# 11-Ice40_FPGA.net
KiCad netlist of a schematic drawn in Altium Designer
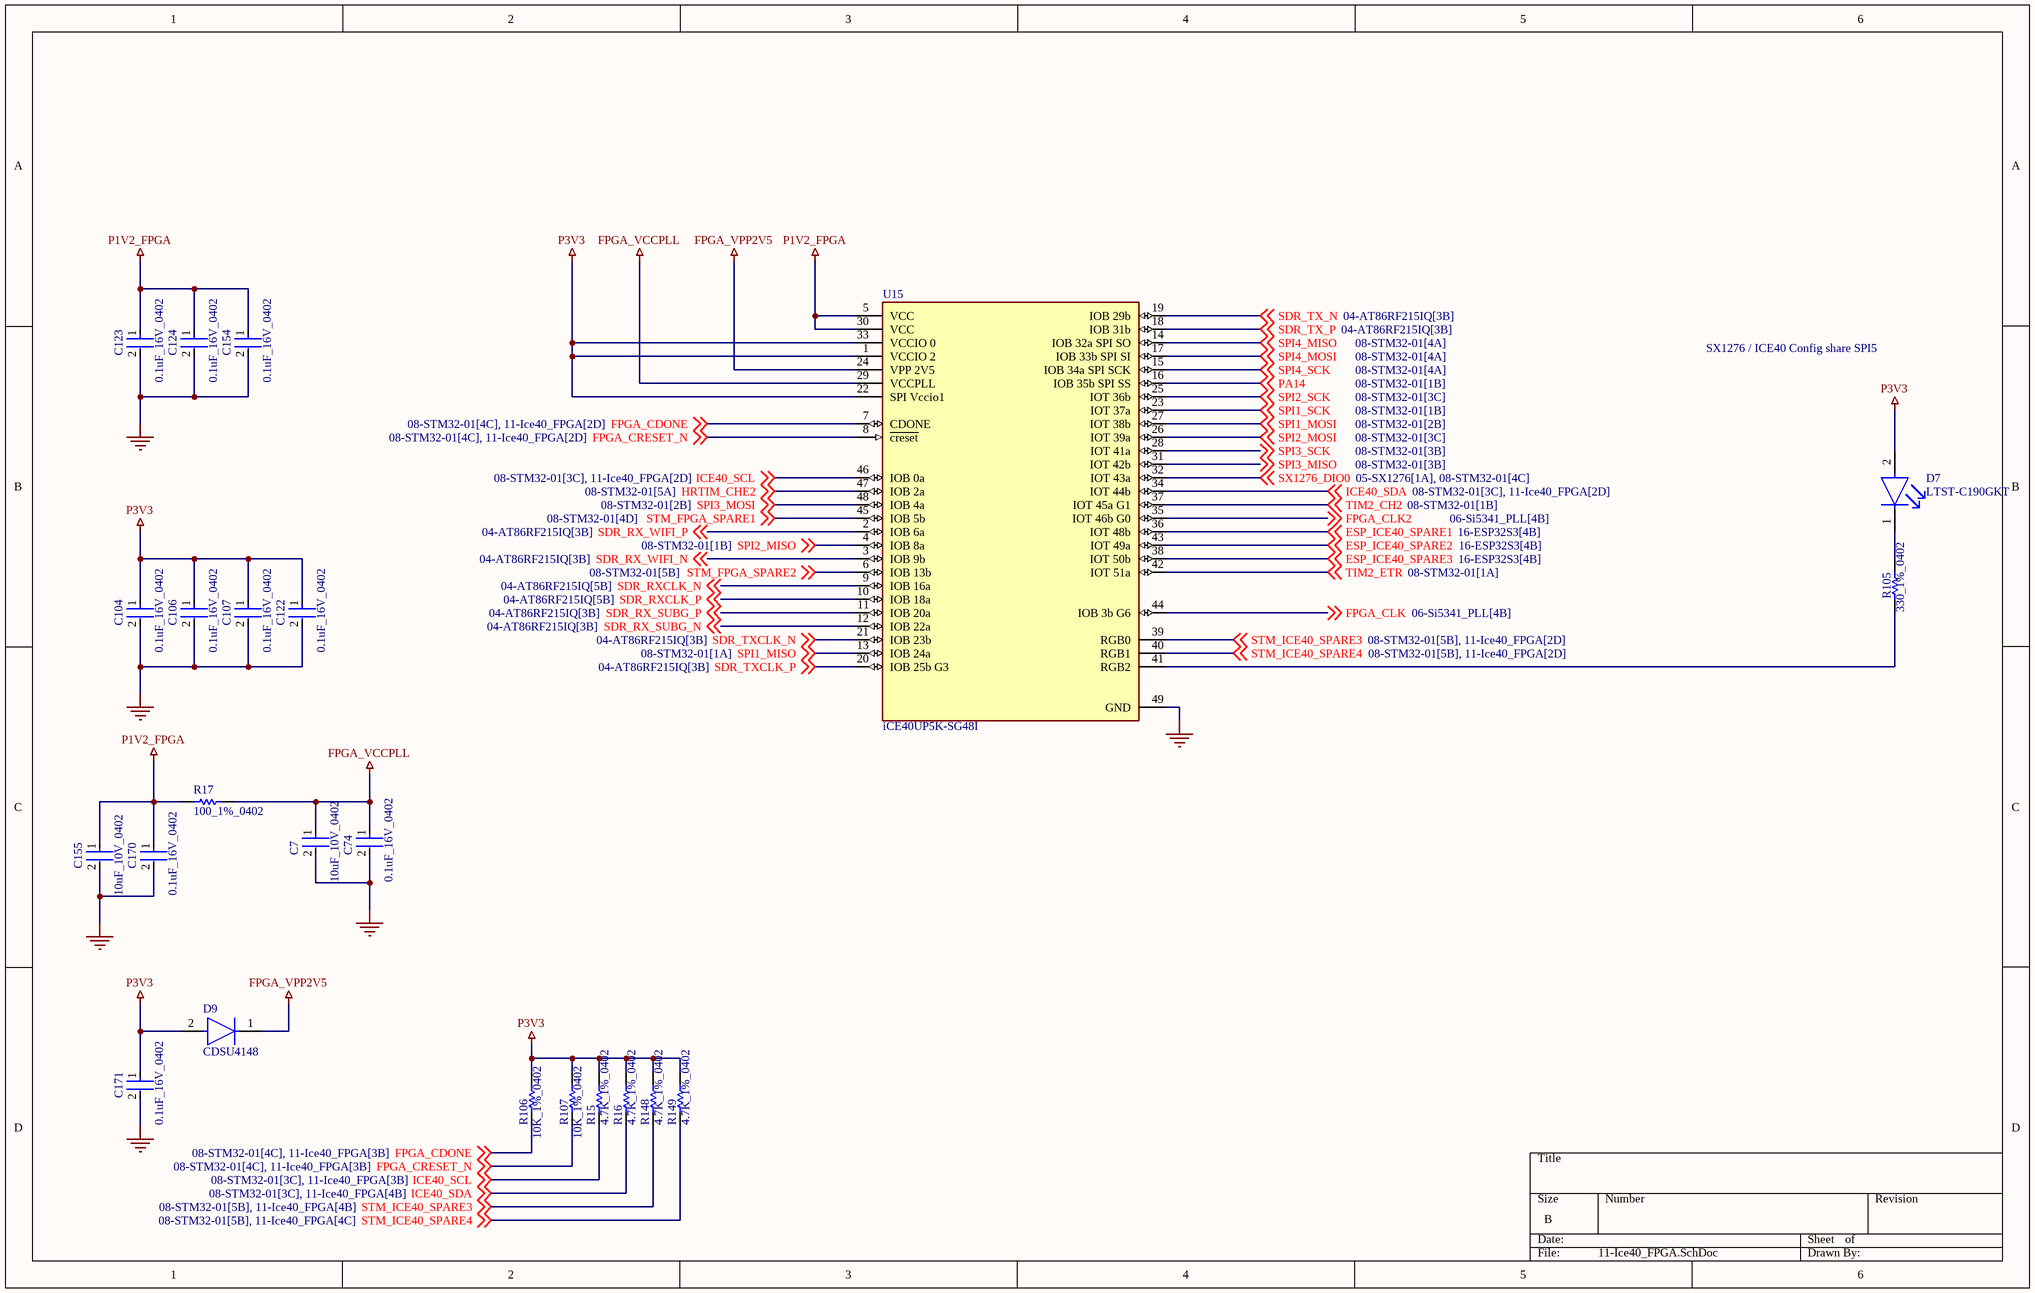
[diagram p0: 11-Ice40_FPGA.SchDoc]

(export (version "E")
  (design (tool "Eeschema 10.0.6"))
  (components
    (comp (ref "C7")
      (value "10uF_10V_0402")
      (footprint "FP-CL05A106MP5NUNC-MFG")
      (description "CAP CER 10UF 10V X5R 0402")
      (fields
        (field (name "OCTOPART") "https://octopart.com/cl05a106mp5nunc-samsung-22457395")
        (field (name "TOLERANCE") "20%")
      )
      (libsource (lib "Altium Content Vault") (part "b4654b650e69147ec39a6b967a45e02"))
    )
    (comp (ref "C74")
      (value "0.1uF_16V_0402")
      (footprint "FP-C0402-BB-MFG")
      (description "CAP CER 0.1UF 16V 5% X7R 0402")
      (fields
        (field (name "MANUFACTURER") "Kemet")
        (field (name "MANUFACTURER PART NUMBER") "C0402C104J4RACTU")
      )
      (libsource (lib "Altium Content Vault") (part "b4654b650e69147ec39a6b967a45e02"))
    )
    (comp (ref "C104")
      (value "0.1uF_16V_0402")
      (footprint "FP-C0402-BB-MFG")
      (description "CAP CER 0.1UF 16V 5% X7R 0402")
      (fields
        (field (name "MANUFACTURER") "Kemet")
        (field (name "MANUFACTURER PART NUMBER") "C0402C104J4RACTU")
      )
      (libsource (lib "Altium Content Vault") (part "b4654b650e69147ec39a6b967a45e02"))
    )
    (comp (ref "C106")
      (value "0.1uF_16V_0402")
      (footprint "FP-C0402-BB-MFG")
      (description "CAP CER 0.1UF 16V 5% X7R 0402")
      (fields
        (field (name "MANUFACTURER") "Kemet")
        (field (name "MANUFACTURER PART NUMBER") "C0402C104J4RACTU")
      )
      (libsource (lib "Altium Content Vault") (part "b4654b650e69147ec39a6b967a45e02"))
    )
    (comp (ref "C107")
      (value "0.1uF_16V_0402")
      (footprint "FP-C0402-BB-MFG")
      (description "CAP CER 0.1UF 16V 5% X7R 0402")
      (fields
        (field (name "MANUFACTURER") "Kemet")
        (field (name "MANUFACTURER PART NUMBER") "C0402C104J4RACTU")
      )
      (libsource (lib "Altium Content Vault") (part "b4654b650e69147ec39a6b967a45e02"))
    )
    (comp (ref "C122")
      (value "0.1uF_16V_0402")
      (footprint "FP-C0402-BB-MFG")
      (description "CAP CER 0.1UF 16V 5% X7R 0402")
      (fields
        (field (name "MANUFACTURER") "Kemet")
        (field (name "MANUFACTURER PART NUMBER") "C0402C104J4RACTU")
      )
      (libsource (lib "Altium Content Vault") (part "b4654b650e69147ec39a6b967a45e02"))
    )
    (comp (ref "C123")
      (value "0.1uF_16V_0402")
      (footprint "FP-C0402-BB-MFG")
      (description "CAP CER 0.1UF 16V 5% X7R 0402")
      (fields
        (field (name "MANUFACTURER") "Kemet")
        (field (name "MANUFACTURER PART NUMBER") "C0402C104J4RACTU")
      )
      (libsource (lib "Altium Content Vault") (part "b4654b650e69147ec39a6b967a45e02"))
    )
    (comp (ref "C124")
      (value "0.1uF_16V_0402")
      (footprint "FP-C0402-BB-MFG")
      (description "CAP CER 0.1UF 16V 5% X7R 0402")
      (fields
        (field (name "MANUFACTURER") "Kemet")
        (field (name "MANUFACTURER PART NUMBER") "C0402C104J4RACTU")
      )
      (libsource (lib "Altium Content Vault") (part "b4654b650e69147ec39a6b967a45e02"))
    )
    (comp (ref "C154")
      (value "0.1uF_16V_0402")
      (footprint "FP-C0402-BB-MFG")
      (description "CAP CER 0.1UF 16V 5% X7R 0402")
      (fields
        (field (name "MANUFACTURER") "Kemet")
        (field (name "MANUFACTURER PART NUMBER") "C0402C104J4RACTU")
      )
      (libsource (lib "Altium Content Vault") (part "b4654b650e69147ec39a6b967a45e02"))
    )
    (comp (ref "C155")
      (value "10uF_10V_0402")
      (footprint "FP-CL05A106MP5NUNC-MFG")
      (description "CAP CER 10UF 10V X5R 0402")
      (fields
        (field (name "OCTOPART") "https://octopart.com/cl05a106mp5nunc-samsung-22457395")
        (field (name "TOLERANCE") "20%")
      )
      (libsource (lib "Altium Content Vault") (part "b4654b650e69147ec39a6b967a45e02"))
    )
    (comp (ref "C170")
      (value "0.1uF_16V_0402")
      (footprint "FP-C0402-BB-MFG")
      (description "CAP CER 0.1UF 16V 5% X7R 0402")
      (fields
        (field (name "MANUFACTURER") "Kemet")
        (field (name "MANUFACTURER PART NUMBER") "C0402C104J4RACTU")
      )
      (libsource (lib "Altium Content Vault") (part "b4654b650e69147ec39a6b967a45e02"))
    )
    (comp (ref "C171")
      (value "0.1uF_16V_0402")
      (footprint "FP-C0402-BB-MFG")
      (description "CAP CER 0.1UF 16V 5% X7R 0402")
      (fields
        (field (name "MANUFACTURER") "Kemet")
        (field (name "MANUFACTURER PART NUMBER") "C0402C104J4RACTU")
      )
      (libsource (lib "Altium Content Vault") (part "b4654b650e69147ec39a6b967a45e02"))
    )
    (comp (ref "D7")
      (value "LTST-C190GKT")
      (footprint "FP-LTST-C190GKT-MFG")
      (description "LED GREEN CLEAR CHIP SMD")
      (fields (field (name "VOLTAGE") "2V"))
      (libsource (lib "Altium Content Vault") (part "8706943c75ba83719d021d2fdc84c58"))
    )
    (comp (ref "D9")
      (value "CDSU4148")
      (footprint "FP-0603-SOD-523F-MFG")
      (description "DIODE GEN PURP 75V 150MA 0603")
      (libsource (lib "Altium Content Vault") (part "d7152d700b627762746794eb795d46e"))
    )
    (comp (ref "R15")
      (value "4.7K_1%_0402")
      (footprint "RESC1005X40X25NL10T10")
      (fields (field (name "MANUFACTURER") "Bourns") (field (name "PART NUMBER") "CR0402-FX-4701GLF"))
      (libsource (lib "Altium Content Vault") (part "RES"))
    )
    (comp (ref "R16")
      (value "4.7K_1%_0402")
      (footprint "RESC1005X40X25NL10T10")
      (fields (field (name "MANUFACTURER") "Bourns") (field (name "PART NUMBER") "CR0402-FX-4701GLF"))
      (libsource (lib "Altium Content Vault") (part "RES"))
    )
    (comp (ref "R17")
      (value "100_1%_0402")
      (footprint "RESC1005X40X25LL05T05")
      (description "Chip Resistor, 100 Ohm, +/- 1%, 100 mW, -55 to 155 degC, 0402 (1005 Metric), RoHS, Tape and Reel")
      (fields (field (name "MANUFACTURER") "Basic Passives") (field (name "TOLERANCE") "1%"))
      (libsource (lib "Altium Content Vault") (part "RES-2"))
    )
    (comp (ref "R105")
      (value "330_1%_0402")
      (footprint "RESC1005X40X25NL10T10")
      (fields (field (name "MANUFACTURER") "Panasonic") (field (name "PART NUMBER") "ERA-2AED331X"))
      (libsource (lib "Altium Content Vault") (part "RES"))
    )
    (comp (ref "R106")
      (value "10K_1%_0402")
      (footprint "RESC1005X40X25NL10T10")
      (fields (field (name "MANUFACTURER") "Bourns") (field (name "PART NUMBER") "CR0402-FX-1002GLF"))
      (libsource (lib "Altium Content Vault") (part "RES"))
    )
    (comp (ref "R107")
      (value "10K_1%_0402")
      (footprint "RESC1005X40X25NL10T10")
      (fields (field (name "MANUFACTURER") "Bourns") (field (name "PART NUMBER") "CR0402-FX-1002GLF"))
      (libsource (lib "Altium Content Vault") (part "RES"))
    )
    (comp (ref "R148")
      (value "4.7K_1%_0402")
      (footprint "RESC1005X40X25NL10T10")
      (fields (field (name "MANUFACTURER") "Bourns") (field (name "PART NUMBER") "CR0402-FX-4701GLF"))
      (libsource (lib "Altium Content Vault") (part "RES"))
    )
    (comp (ref "R149")
      (value "4.7K_1%_0402")
      (footprint "RESC1005X40X25NL10T10")
      (fields (field (name "MANUFACTURER") "Bourns") (field (name "PART NUMBER") "CR0402-FX-4701GLF"))
      (libsource (lib "Altium Content Vault") (part "RES"))
    )
    (comp (ref "U15")
      (value "iCE40UP5K-SG48I")
      (footprint "FP-QFN-48-IPC_C")
      (description "ICE40-ULTRAPLUS, 5280 LUTS, 1.2V")
      (fields
        (field (name "MANUFACTURER") "Lattice")
        (field (name "OCTOPART") "https://octopart.com/ice40up5k-sg48i-lattice+semiconductor-87369311")
      )
      (libsource (lib "Altium Content Vault") (part "90c839ece6b9b86f6dd6a74a4566a88"))
    )
  )
  (nets
    (net (code "1") (name "ESP_ICE40_SPARE1") (class "Default")
      (node (ref "U15") (pin "36") (pinfunction "IOT_48b_36") (pintype "bidirectional"))
    )
    (net (code "2") (name "ESP_ICE40_SPARE2") (class "Default")
      (node (ref "U15") (pin "43") (pinfunction "IOT_49a_43") (pintype "bidirectional"))
    )
    (net (code "3") (name "ESP_ICE40_SPARE3") (class "Default")
      (node (ref "U15") (pin "38") (pinfunction "IOT_50b_38") (pintype "bidirectional"))
    )
    (net (code "4") (name "FPGA_CDONE") (class "Default")
      (node (ref "R106") (pin "1") (pinfunction "1_1") (pintype "passive"))
      (node (ref "U15") (pin "7") (pinfunction "CDONE_7") (pintype "bidirectional"))
    )
    (net (code "5") (name "FPGA_CLK") (class "Default")
      (node (ref "U15") (pin "44") (pinfunction "IOB_3b_G6_44") (pintype "bidirectional"))
    )
    (net (code "6") (name "FPGA_CLK2") (class "Default")
      (node (ref "U15") (pin "35") (pinfunction "IOT_46b_G0_35") (pintype "bidirectional"))
    )
    (net (code "7") (name "FPGA_CRESET_N") (class "Default")
      (node (ref "R107") (pin "1") (pinfunction "1_1") (pintype "passive"))
      (node (ref "U15") (pin "8") (pinfunction "~{creset}_8") (pintype "input"))
    )
    (net (code "8") (name "FPGA_VCCPLL") (class "Default")
      (node (ref "C7") (pin "1") (pinfunction "1_1") (pintype "passive"))
      (node (ref "C74") (pin "1") (pinfunction "1_1") (pintype "passive"))
      (node (ref "R17") (pin "2") (pinfunction "2_2") (pintype "passive"))
      (node (ref "U15") (pin "29") (pinfunction "VCCPLL_29") (pintype "power_in"))
    )
    (net (code "9") (name "FPGA_VPP2V5") (class "Default")
      (node (ref "D9") (pin "1") (pinfunction "C_1") (pintype "passive"))
      (node (ref "U15") (pin "24") (pinfunction "VPP_2V5_24") (pintype "power_in"))
    )
    (net (code "10") (name "GND") (class "Default")
      (node (ref "C104") (pin "2") (pinfunction "2_2") (pintype "passive"))
      (node (ref "C106") (pin "2") (pinfunction "2_2") (pintype "passive"))
      (node (ref "C107") (pin "2") (pinfunction "2_2") (pintype "passive"))
      (node (ref "C122") (pin "2") (pinfunction "2_2") (pintype "passive"))
      (node (ref "C123") (pin "2") (pinfunction "2_2") (pintype "passive"))
      (node (ref "C124") (pin "2") (pinfunction "2_2") (pintype "passive"))
      (node (ref "C154") (pin "2") (pinfunction "2_2") (pintype "passive"))
      (node (ref "C155") (pin "2") (pinfunction "2_2") (pintype "passive"))
      (node (ref "C170") (pin "2") (pinfunction "2_2") (pintype "passive"))
      (node (ref "C171") (pin "2") (pinfunction "2_2") (pintype "passive"))
      (node (ref "C7") (pin "2") (pinfunction "2_2") (pintype "passive"))
      (node (ref "C74") (pin "2") (pinfunction "2_2") (pintype "passive"))
      (node (ref "U15") (pin "49") (pinfunction "GND_49") (pintype "power_in"))
    )
    (net (code "11") (name "HRTIM_CHE2") (class "Default")
      (node (ref "U15") (pin "47") (pinfunction "IOB_2a_47") (pintype "bidirectional"))
    )
    (net (code "12") (name "ICE40_SCL") (class "Default")
      (node (ref "R15") (pin "1") (pinfunction "1_1") (pintype "passive"))
      (node (ref "U15") (pin "46") (pinfunction "IOB_0a_46") (pintype "bidirectional"))
    )
    (net (code "13") (name "ICE40_SDA") (class "Default")
      (node (ref "R16") (pin "1") (pinfunction "1_1") (pintype "passive"))
      (node (ref "U15") (pin "34") (pinfunction "IOT_44b_34") (pintype "bidirectional"))
    )
    (net (code "14") (name "Net-(D7-C)") (class "Default")
      (node (ref "D7") (pin "1") (pinfunction "C_1") (pintype "passive"))
      (node (ref "R105") (pin "2") (pinfunction "2_2") (pintype "passive"))
    )
    (net (code "15") (name "Net-(U15-RGB2)") (class "Default")
      (node (ref "R105") (pin "1") (pinfunction "1_1") (pintype "passive"))
      (node (ref "U15") (pin "41") (pinfunction "RGB2_41") (pintype "open_collector"))
    )
    (net (code "16") (name "P1V2_FPGA") (class "Default")
      (node (ref "C123") (pin "1") (pinfunction "1_1") (pintype "passive"))
      (node (ref "C124") (pin "1") (pinfunction "1_1") (pintype "passive"))
      (node (ref "C154") (pin "1") (pinfunction "1_1") (pintype "passive"))
      (node (ref "C155") (pin "1") (pinfunction "1_1") (pintype "passive"))
      (node (ref "C170") (pin "1") (pinfunction "1_1") (pintype "passive"))
      (node (ref "R17") (pin "1") (pinfunction "1_1") (pintype "passive"))
      (node (ref "U15") (pin "30") (pinfunction "VCC_30") (pintype "power_in"))
      (node (ref "U15") (pin "5") (pinfunction "VCC_5") (pintype "power_in"))
    )
    (net (code "17") (name "P3V3") (class "Default")
      (node (ref "C104") (pin "1") (pinfunction "1_1") (pintype "passive"))
      (node (ref "C106") (pin "1") (pinfunction "1_1") (pintype "passive"))
      (node (ref "C107") (pin "1") (pinfunction "1_1") (pintype "passive"))
      (node (ref "C122") (pin "1") (pinfunction "1_1") (pintype "passive"))
      (node (ref "C171") (pin "1") (pinfunction "1_1") (pintype "passive"))
      (node (ref "D7") (pin "2") (pinfunction "A_2") (pintype "passive"))
      (node (ref "D9") (pin "2") (pinfunction "A_2") (pintype "passive"))
      (node (ref "R106") (pin "2") (pinfunction "2_2") (pintype "passive"))
      (node (ref "R107") (pin "2") (pinfunction "2_2") (pintype "passive"))
      (node (ref "R148") (pin "2") (pinfunction "2_2") (pintype "passive"))
      (node (ref "R149") (pin "2") (pinfunction "2_2") (pintype "passive"))
      (node (ref "R15") (pin "2") (pinfunction "2_2") (pintype "passive"))
      (node (ref "R16") (pin "2") (pinfunction "2_2") (pintype "passive"))
      (node (ref "U15") (pin "1") (pinfunction "VCCIO_2_1") (pintype "power_in"))
      (node (ref "U15") (pin "22") (pinfunction "SPI_Vccio1_22") (pintype "power_in"))
      (node (ref "U15") (pin "33") (pinfunction "VCCIO_0_33") (pintype "power_in"))
    )
    (net (code "18") (name "PA14") (class "Default")
      (node (ref "U15") (pin "16") (pinfunction "IOB_35b_SPI_SS_16") (pintype "bidirectional"))
    )
    (net (code "19") (name "SDR_RXCLK_N") (class "Default")
      (node (ref "U15") (pin "9") (pinfunction "IOB_16a_9") (pintype "bidirectional"))
    )
    (net (code "20") (name "SDR_RXCLK_P") (class "Default")
      (node (ref "U15") (pin "10") (pinfunction "IOB_18a_10") (pintype "bidirectional"))
    )
    (net (code "21") (name "SDR_RX_SUBG_N") (class "Default")
      (node (ref "U15") (pin "12") (pinfunction "IOB_22a_12") (pintype "bidirectional"))
    )
    (net (code "22") (name "SDR_RX_SUBG_P") (class "Default")
      (node (ref "U15") (pin "11") (pinfunction "IOB_20a_11") (pintype "bidirectional"))
    )
    (net (code "23") (name "SDR_RX_WIFI_N") (class "Default")
      (node (ref "U15") (pin "3") (pinfunction "IOB_9b_3") (pintype "bidirectional"))
    )
    (net (code "24") (name "SDR_RX_WIFI_P") (class "Default")
      (node (ref "U15") (pin "2") (pinfunction "IOB_6a_2") (pintype "bidirectional"))
    )
    (net (code "25") (name "SDR_TXCLK_N") (class "Default")
      (node (ref "U15") (pin "21") (pinfunction "IOB_23b_21") (pintype "bidirectional"))
    )
    (net (code "26") (name "SDR_TXCLK_P") (class "Default")
      (node (ref "U15") (pin "20") (pinfunction "IOB_25b_G3_20") (pintype "bidirectional"))
    )
    (net (code "27") (name "SDR_TX_N") (class "Default")
      (node (ref "U15") (pin "19") (pinfunction "IOB_29b_19") (pintype "bidirectional"))
    )
    (net (code "28") (name "SDR_TX_P") (class "Default")
      (node (ref "U15") (pin "18") (pinfunction "IOB_31b_18") (pintype "bidirectional"))
    )
    (net (code "29") (name "SPI1_MISO") (class "Default")
      (node (ref "U15") (pin "13") (pinfunction "IOB_24a_13") (pintype "bidirectional"))
    )
    (net (code "30") (name "SPI1_MOSI") (class "Default")
      (node (ref "U15") (pin "27") (pinfunction "IOT_38b_27") (pintype "bidirectional"))
    )
    (net (code "31") (name "SPI1_SCK") (class "Default")
      (node (ref "U15") (pin "23") (pinfunction "IOT_37a_23") (pintype "bidirectional"))
    )
    (net (code "32") (name "SPI2_MISO") (class "Default")
      (node (ref "U15") (pin "4") (pinfunction "IOB_8a_4") (pintype "bidirectional"))
    )
    (net (code "33") (name "SPI2_MOSI") (class "Default")
      (node (ref "U15") (pin "26") (pinfunction "IOT_39a_26") (pintype "bidirectional"))
    )
    (net (code "34") (name "SPI2_SCK") (class "Default")
      (node (ref "U15") (pin "25") (pinfunction "IOT_36b_25") (pintype "bidirectional"))
    )
    (net (code "35") (name "SPI3_MISO") (class "Default")
      (node (ref "U15") (pin "31") (pinfunction "IOT_42b_31") (pintype "bidirectional"))
    )
    (net (code "36") (name "SPI3_MOSI") (class "Default")
      (node (ref "U15") (pin "48") (pinfunction "IOB_4a_48") (pintype "bidirectional"))
    )
    (net (code "37") (name "SPI3_SCK") (class "Default")
      (node (ref "U15") (pin "28") (pinfunction "IOT_41a_28") (pintype "bidirectional"))
    )
    (net (code "38") (name "SPI4_MISO") (class "Default")
      (node (ref "U15") (pin "14") (pinfunction "IOB_32a_SPI_SO_14") (pintype "bidirectional"))
    )
    (net (code "39") (name "SPI4_MOSI") (class "Default")
      (node (ref "U15") (pin "17") (pinfunction "IOB_33b_SPI_SI_17") (pintype "bidirectional"))
    )
    (net (code "40") (name "SPI4_SCK") (class "Default")
      (node (ref "U15") (pin "15") (pinfunction "IOB_34a_SPI_SCK_15") (pintype "bidirectional"))
    )
    (net (code "41") (name "STM_FPGA_SPARE1") (class "Default")
      (node (ref "U15") (pin "45") (pinfunction "IOB_5b_45") (pintype "bidirectional"))
    )
    (net (code "42") (name "STM_FPGA_SPARE2") (class "Default")
      (node (ref "U15") (pin "6") (pinfunction "IOB_13b_6") (pintype "bidirectional"))
    )
    (net (code "43") (name "STM_ICE40_SPARE3") (class "Default")
      (node (ref "R148") (pin "1") (pinfunction "1_1") (pintype "passive"))
      (node (ref "U15") (pin "39") (pinfunction "RGB0_39") (pintype "open_collector"))
    )
    (net (code "44") (name "STM_ICE40_SPARE4") (class "Default")
      (node (ref "R149") (pin "1") (pinfunction "1_1") (pintype "passive"))
      (node (ref "U15") (pin "40") (pinfunction "RGB1_40") (pintype "open_collector"))
    )
    (net (code "45") (name "SX1276_DIO0") (class "Default")
      (node (ref "U15") (pin "32") (pinfunction "IOT_43a_32") (pintype "bidirectional"))
    )
    (net (code "46") (name "TIM2_CH2") (class "Default")
      (node (ref "U15") (pin "37") (pinfunction "IOT_45a_G1_37") (pintype "bidirectional"))
    )
    (net (code "47") (name "TIM2_ETR") (class "Default")
      (node (ref "U15") (pin "42") (pinfunction "IOT_51a_42") (pintype "bidirectional"))
    )
  )
)
